# Adafruit_LIS3MDL.net
KiCad netlist of a schematic drawn in EAGLE
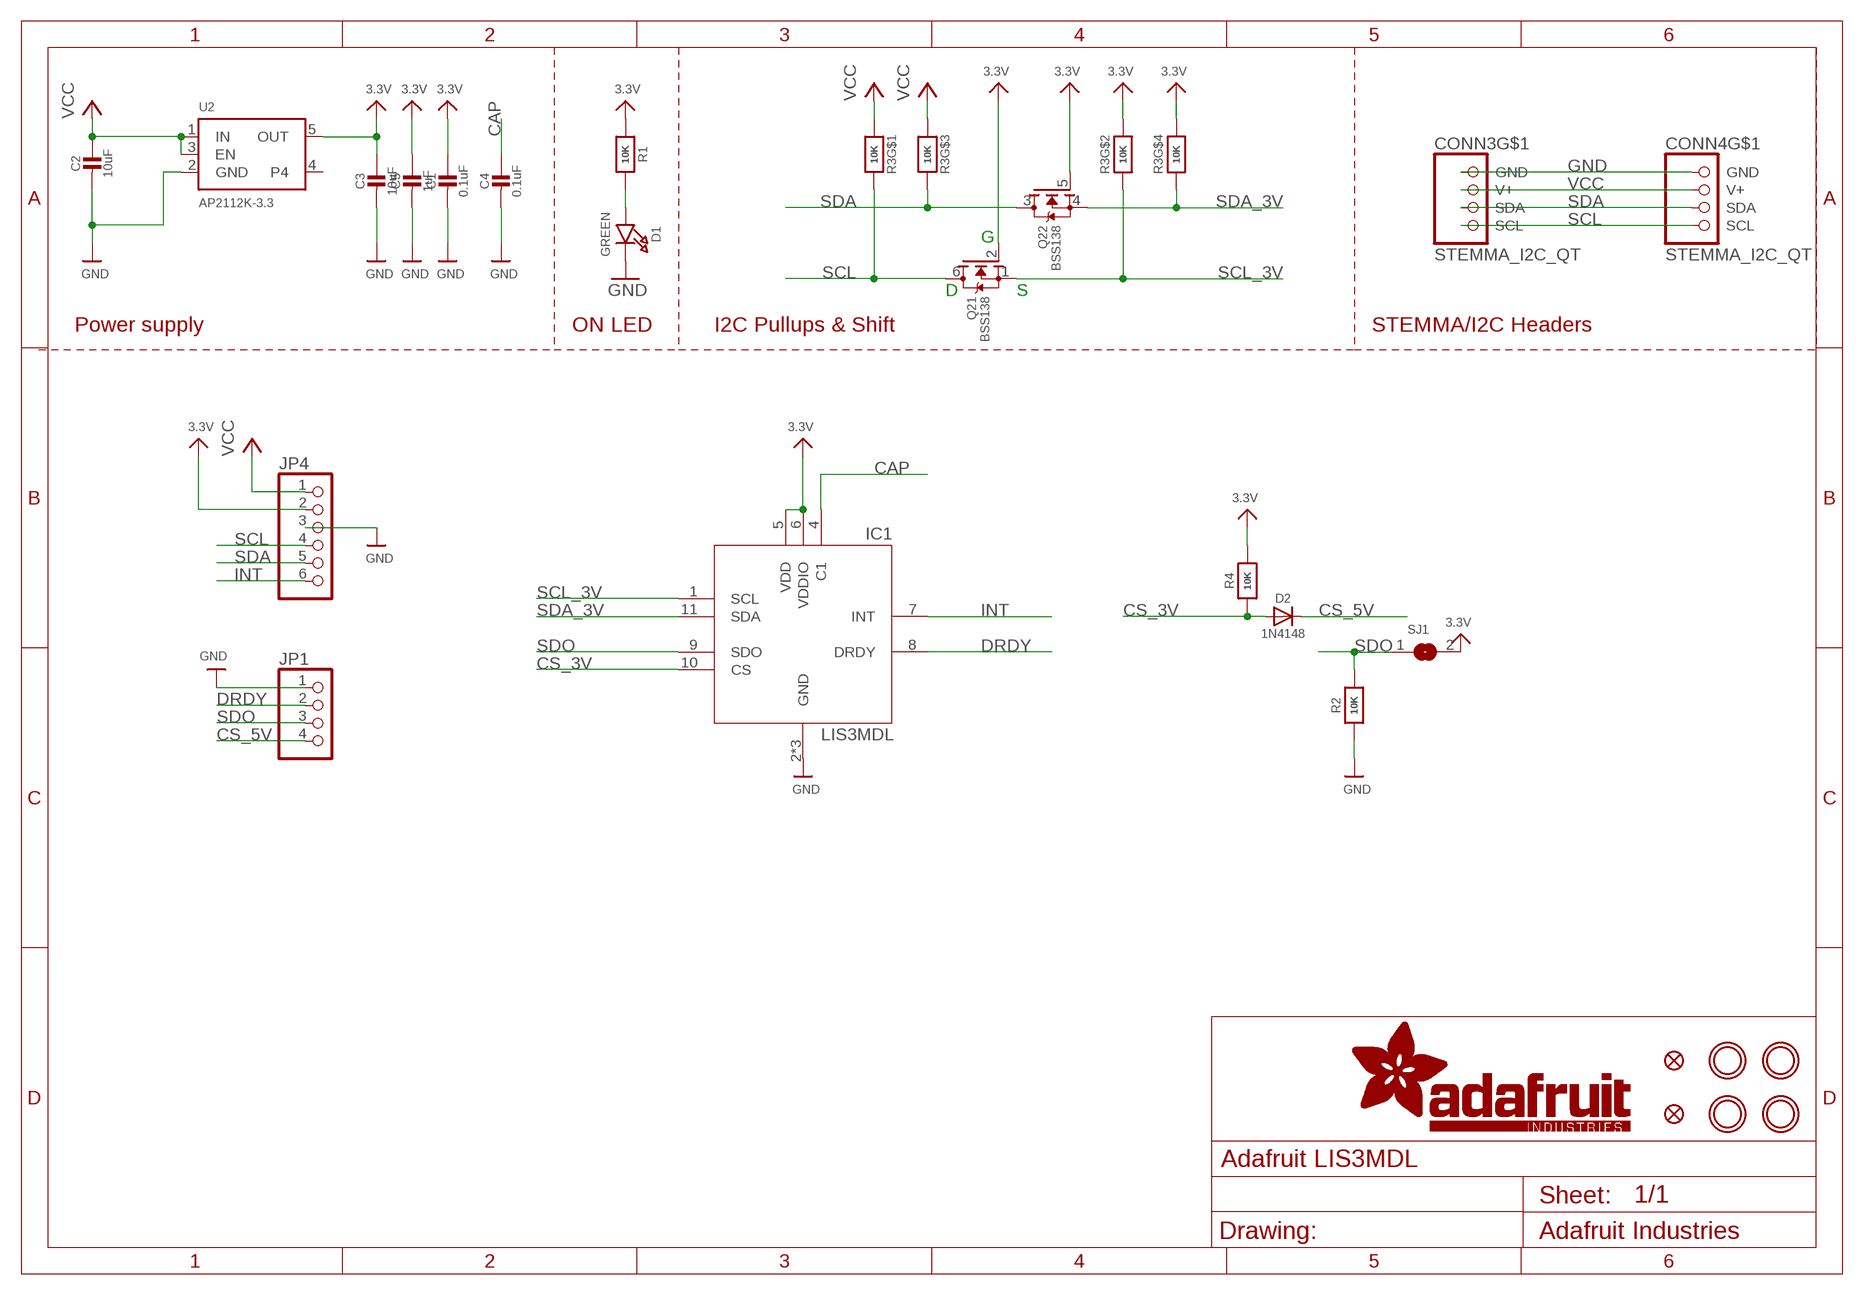
[diagram p0: schematic, sheet 1]

(export (version "E")
  (design (tool "Eeschema 10.0.6"))
  (components
    (comp (ref "C1")
      (value "0.1uF")
      (footprint "eagle-import:0603-NO")
      (libsource (lib "eagle-import") (part "CAP_CERAMIC0603_NO"))
    )
    (comp (ref "C2")
      (value "10uF")
      (footprint "eagle-import:0805-NO")
      (libsource (lib "eagle-import") (part "CAP_CERAMIC0805-NOOUTLINE"))
    )
    (comp (ref "C3")
      (value "10uF")
      (footprint "eagle-import:0805-NO")
      (libsource (lib "eagle-import") (part "CAP_CERAMIC0805-NOOUTLINE"))
    )
    (comp (ref "C4")
      (value "0.1uF")
      (footprint "eagle-import:0603-NO")
      (libsource (lib "eagle-import") (part "CAP_CERAMIC0603_NO"))
    )
    (comp (ref "C5")
      (value "1uF")
      (footprint "eagle-import:0603-NO")
      (libsource (lib "eagle-import") (part "CAP_CERAMIC0603_NO"))
    )
    (comp (ref "CONN3")
      (value "STEMMA_I2C_QT")
      (footprint "eagle-import:JST_SH4")
      (libsource (lib "eagle-import") (part "STEMMA_I2C_QT"))
    )
    (comp (ref "CONN4")
      (value "STEMMA_I2C_QT")
      (footprint "eagle-import:JST_SH4")
      (libsource (lib "eagle-import") (part "STEMMA_I2C_QT"))
    )
    (comp (ref "D1")
      (value "GREEN")
      (footprint "eagle-import:CHIPLED_0603_NOOUTLINE")
      (libsource (lib "eagle-import") (part "LED0603_NOOUTLINE"))
    )
    (comp (ref "D2")
      (value "1N4148")
      (footprint "eagle-import:SOD-323")
      (libsource (lib "eagle-import") (part "DIODESOD-323"))
    )
    (comp (ref "FID3")
      (value "FIDUCIAL_1MM")
      (footprint "eagle-import:FIDUCIAL_1MM")
      (libsource (lib "eagle-import") (part "FIDUCIAL_1MM"))
    )
    (comp (ref "FID4")
      (value "FIDUCIAL_1MM")
      (footprint "eagle-import:FIDUCIAL_1MM")
      (libsource (lib "eagle-import") (part "FIDUCIAL_1MM"))
    )
    (comp (ref "IC1")
      (value "LIS3MDL")
      (footprint "eagle-import:LGA12_2X2MM")
      (libsource (lib "eagle-import") (part "LIS3MDL"))
    )
    (comp (ref "JP1")
      (value "HEADER-1X4ROUND")
      (footprint "eagle-import:1X04_ROUND")
      (libsource (lib "eagle-import") (part "HEADER-1X4ROUND"))
    )
    (comp (ref "JP4")
      (value "HEADER-1X670MIL")
      (footprint "eagle-import:1X06_ROUND_70")
      (libsource (lib "eagle-import") (part "HEADER-1X670MIL"))
    )
    (comp (ref "Q2")
      (value "BSS138")
      (footprint "eagle-import:SOT363")
      (libsource (lib "eagle-import") (part "MOSFET-N_DUAL"))
    )
    (comp (ref "R1")
      (value "10K")
      (footprint "eagle-import:0603-NO")
      (libsource (lib "eagle-import") (part "RESISTOR_0603_NOOUT"))
    )
    (comp (ref "R2")
      (value "10K")
      (footprint "eagle-import:0603-NO")
      (libsource (lib "eagle-import") (part "RESISTOR_0603_NOOUT"))
    )
    (comp (ref "R3")
      (value "10K")
      (footprint "eagle-import:RESPACK_4X0603")
      (libsource (lib "eagle-import") (part "RESISTOR_4PACK"))
    )
    (comp (ref "R4")
      (value "10K")
      (footprint "eagle-import:0603-NO")
      (libsource (lib "eagle-import") (part "RESISTOR_0603_NOOUT"))
    )
    (comp (ref "SJ1")
      (value "SOLDERJUMPER")
      (footprint "eagle-import:SOLDERJUMPER_ARROW_NOPASTE")
      (libsource (lib "eagle-import") (part "SOLDERJUMPER"))
    )
    (comp (ref "U$1")
      (value "MOUNTINGHOLE2.5")
      (footprint "eagle-import:MOUNTINGHOLE_2.5_PLATED")
      (libsource (lib "eagle-import") (part "MOUNTINGHOLE2.5"))
    )
    (comp (ref "U$17")
      (value "MOUNTINGHOLE2.5")
      (footprint "eagle-import:MOUNTINGHOLE_2.5_PLATED")
      (libsource (lib "eagle-import") (part "MOUNTINGHOLE2.5"))
    )
    (comp (ref "U$19")
      (value "MOUNTINGHOLE2.5")
      (footprint "eagle-import:MOUNTINGHOLE_2.5_PLATED")
      (libsource (lib "eagle-import") (part "MOUNTINGHOLE2.5"))
    )
    (comp (ref "U$21")
      (value "MOUNTINGHOLE2.5")
      (footprint "eagle-import:MOUNTINGHOLE_2.5_PLATED")
      (libsource (lib "eagle-import") (part "MOUNTINGHOLE2.5"))
    )
    (comp (ref "U2")
      (value "AP2112K-3.3")
      (footprint "eagle-import:SOT23-5")
      (libsource (lib "eagle-import") (part "VREG_SOT23-5"))
    )
  )
  (nets
    (net (code "1") (name "/CAP") (class "Default")
      (node (ref "C4") (pin "1") (pinfunction "1_1") (pintype "passive"))
      (node (ref "IC1") (pin "4") (pinfunction "C1_4") (pintype "input"))
    )
    (net (code "2") (name "/CS_3V") (class "Default")
      (node (ref "D2") (pin "A") (pinfunction "A_A") (pintype "passive"))
      (node (ref "IC1") (pin "10") (pinfunction "CS_10") (pintype "input"))
      (node (ref "R4") (pin "1") (pinfunction "1_1") (pintype "passive"))
    )
    (net (code "3") (name "/CS_5V") (class "Default")
      (node (ref "D2") (pin "C") (pinfunction "C_C") (pintype "passive"))
      (node (ref "JP1") (pin "4") (pinfunction "4_4") (pintype "passive"))
    )
    (net (code "4") (name "/DRDY") (class "Default")
      (node (ref "IC1") (pin "8") (pinfunction "DRDY_8") (pintype "output"))
      (node (ref "JP1") (pin "2") (pinfunction "2_2") (pintype "passive"))
    )
    (net (code "5") (name "/INT") (class "Default")
      (node (ref "IC1") (pin "7") (pinfunction "INT_7") (pintype "output"))
      (node (ref "JP4") (pin "6") (pinfunction "6_6") (pintype "passive"))
    )
    (net (code "6") (name "/SCL") (class "Default")
      (node (ref "CONN3") (pin "4") (pinfunction "SCL_4") (pintype "passive"))
      (node (ref "CONN4") (pin "4") (pinfunction "SCL_4") (pintype "passive"))
      (node (ref "JP4") (pin "4") (pinfunction "4_4") (pintype "passive"))
      (node (ref "Q2") (pin "6") (pinfunction "D_6") (pintype "bidirectional"))
      (node (ref "R3") (pin "8") (pinfunction "2_8") (pintype "passive"))
    )
    (net (code "7") (name "/SCL_3V") (class "Default")
      (node (ref "IC1") (pin "1") (pinfunction "SCL_1") (pintype "input"))
      (node (ref "Q2") (pin "1") (pinfunction "S_1") (pintype "bidirectional"))
      (node (ref "R3") (pin "7") (pinfunction "2_7") (pintype "passive"))
    )
    (net (code "8") (name "/SDA") (class "Default")
      (node (ref "CONN3") (pin "3") (pinfunction "SDA_3") (pintype "passive"))
      (node (ref "CONN4") (pin "3") (pinfunction "SDA_3") (pintype "passive"))
      (node (ref "JP4") (pin "5") (pinfunction "5_5") (pintype "passive"))
      (node (ref "Q2") (pin "3") (pinfunction "D_3") (pintype "bidirectional"))
      (node (ref "R3") (pin "6") (pinfunction "2_6") (pintype "passive"))
    )
    (net (code "9") (name "/SDA_3V") (class "Default")
      (node (ref "IC1") (pin "11") (pinfunction "SDA_11") (pintype "bidirectional"))
      (node (ref "Q2") (pin "4") (pinfunction "S_4") (pintype "bidirectional"))
      (node (ref "R3") (pin "5") (pinfunction "2_5") (pintype "passive"))
    )
    (net (code "10") (name "/SDO") (class "Default")
      (node (ref "IC1") (pin "9") (pinfunction "SDO_9") (pintype "bidirectional"))
      (node (ref "JP1") (pin "3") (pinfunction "3_3") (pintype "passive"))
      (node (ref "R2") (pin "2") (pinfunction "2_2") (pintype "passive"))
      (node (ref "SJ1") (pin "1") (pinfunction "1_1") (pintype "passive"))
    )
    (net (code "11") (name "3.3V") (class "Default")
      (node (ref "C1") (pin "1") (pinfunction "1_1") (pintype "passive"))
      (node (ref "C3") (pin "1") (pinfunction "1_1") (pintype "passive"))
      (node (ref "C5") (pin "1") (pinfunction "1_1") (pintype "passive"))
      (node (ref "IC1") (pin "5") (pinfunction "VDD_5") (pintype "power_in"))
      (node (ref "IC1") (pin "6") (pinfunction "VDDIO_6") (pintype "power_in"))
      (node (ref "JP4") (pin "2") (pinfunction "2_2") (pintype "passive"))
      (node (ref "Q2") (pin "2") (pinfunction "G_2") (pintype "bidirectional"))
      (node (ref "Q2") (pin "5") (pinfunction "G_5") (pintype "bidirectional"))
      (node (ref "R1") (pin "1") (pinfunction "1_1") (pintype "passive"))
      (node (ref "R3") (pin "2") (pinfunction "1_2") (pintype "passive"))
      (node (ref "R3") (pin "4") (pinfunction "1_4") (pintype "passive"))
      (node (ref "R4") (pin "2") (pinfunction "2_2") (pintype "passive"))
      (node (ref "SJ1") (pin "2") (pinfunction "2_2") (pintype "passive"))
      (node (ref "U2") (pin "5") (pinfunction "OUT_5") (pintype "power_in"))
    )
    (net (code "12") (name "GND") (class "Default")
      (node (ref "C1") (pin "2") (pinfunction "2_2") (pintype "passive"))
      (node (ref "C2") (pin "2") (pinfunction "2_2") (pintype "passive"))
      (node (ref "C3") (pin "2") (pinfunction "2_2") (pintype "passive"))
      (node (ref "C4") (pin "2") (pinfunction "2_2") (pintype "passive"))
      (node (ref "C5") (pin "2") (pinfunction "2_2") (pintype "passive"))
      (node (ref "CONN3") (pin "1") (pinfunction "GND_1") (pintype "passive"))
      (node (ref "CONN4") (pin "1") (pinfunction "GND_1") (pintype "passive"))
      (node (ref "D1") (pin "C") (pinfunction "C_C") (pintype "passive"))
      (node (ref "IC1") (pin "12") (pinfunction "GND_12") (pintype "power_in"))
      (node (ref "IC1") (pin "2") (pinfunction "GND_2") (pintype "power_in"))
      (node (ref "IC1") (pin "3") (pinfunction "GND_3") (pintype "power_in"))
      (node (ref "JP1") (pin "1") (pinfunction "1_1") (pintype "passive"))
      (node (ref "JP4") (pin "3") (pinfunction "3_3") (pintype "passive"))
      (node (ref "R2") (pin "1") (pinfunction "1_1") (pintype "passive"))
      (node (ref "U2") (pin "2") (pinfunction "GND_2") (pintype "power_in"))
    )
    (net (code "13") (name "Net-(D1-PadA)") (class "Default")
      (node (ref "D1") (pin "A") (pinfunction "A_A") (pintype "passive"))
      (node (ref "R1") (pin "2") (pinfunction "2_2") (pintype "passive"))
    )
    (net (code "14") (name "VCC") (class "Default")
      (node (ref "C2") (pin "1") (pinfunction "1_1") (pintype "passive"))
      (node (ref "CONN3") (pin "2") (pinfunction "V+_2") (pintype "passive"))
      (node (ref "CONN4") (pin "2") (pinfunction "V+_2") (pintype "passive"))
      (node (ref "JP4") (pin "1") (pinfunction "1_1") (pintype "passive"))
      (node (ref "R3") (pin "1") (pinfunction "1_1") (pintype "passive"))
      (node (ref "R3") (pin "3") (pinfunction "1_3") (pintype "passive"))
      (node (ref "U2") (pin "1") (pinfunction "IN_1") (pintype "power_in"))
      (node (ref "U2") (pin "3") (pinfunction "EN_3") (pintype "input"))
    )
    (net (code "15") (name "unconnected-(U2-P4-Pad4)") (class "Default")
      (node (ref "U2") (pin "4") (pinfunction "P4_4") (pintype "bidirectional"))
    )
  )
)
